# Serial_I2C_Bridge.net
KiCad netlist of a schematic drawn in EAGLE
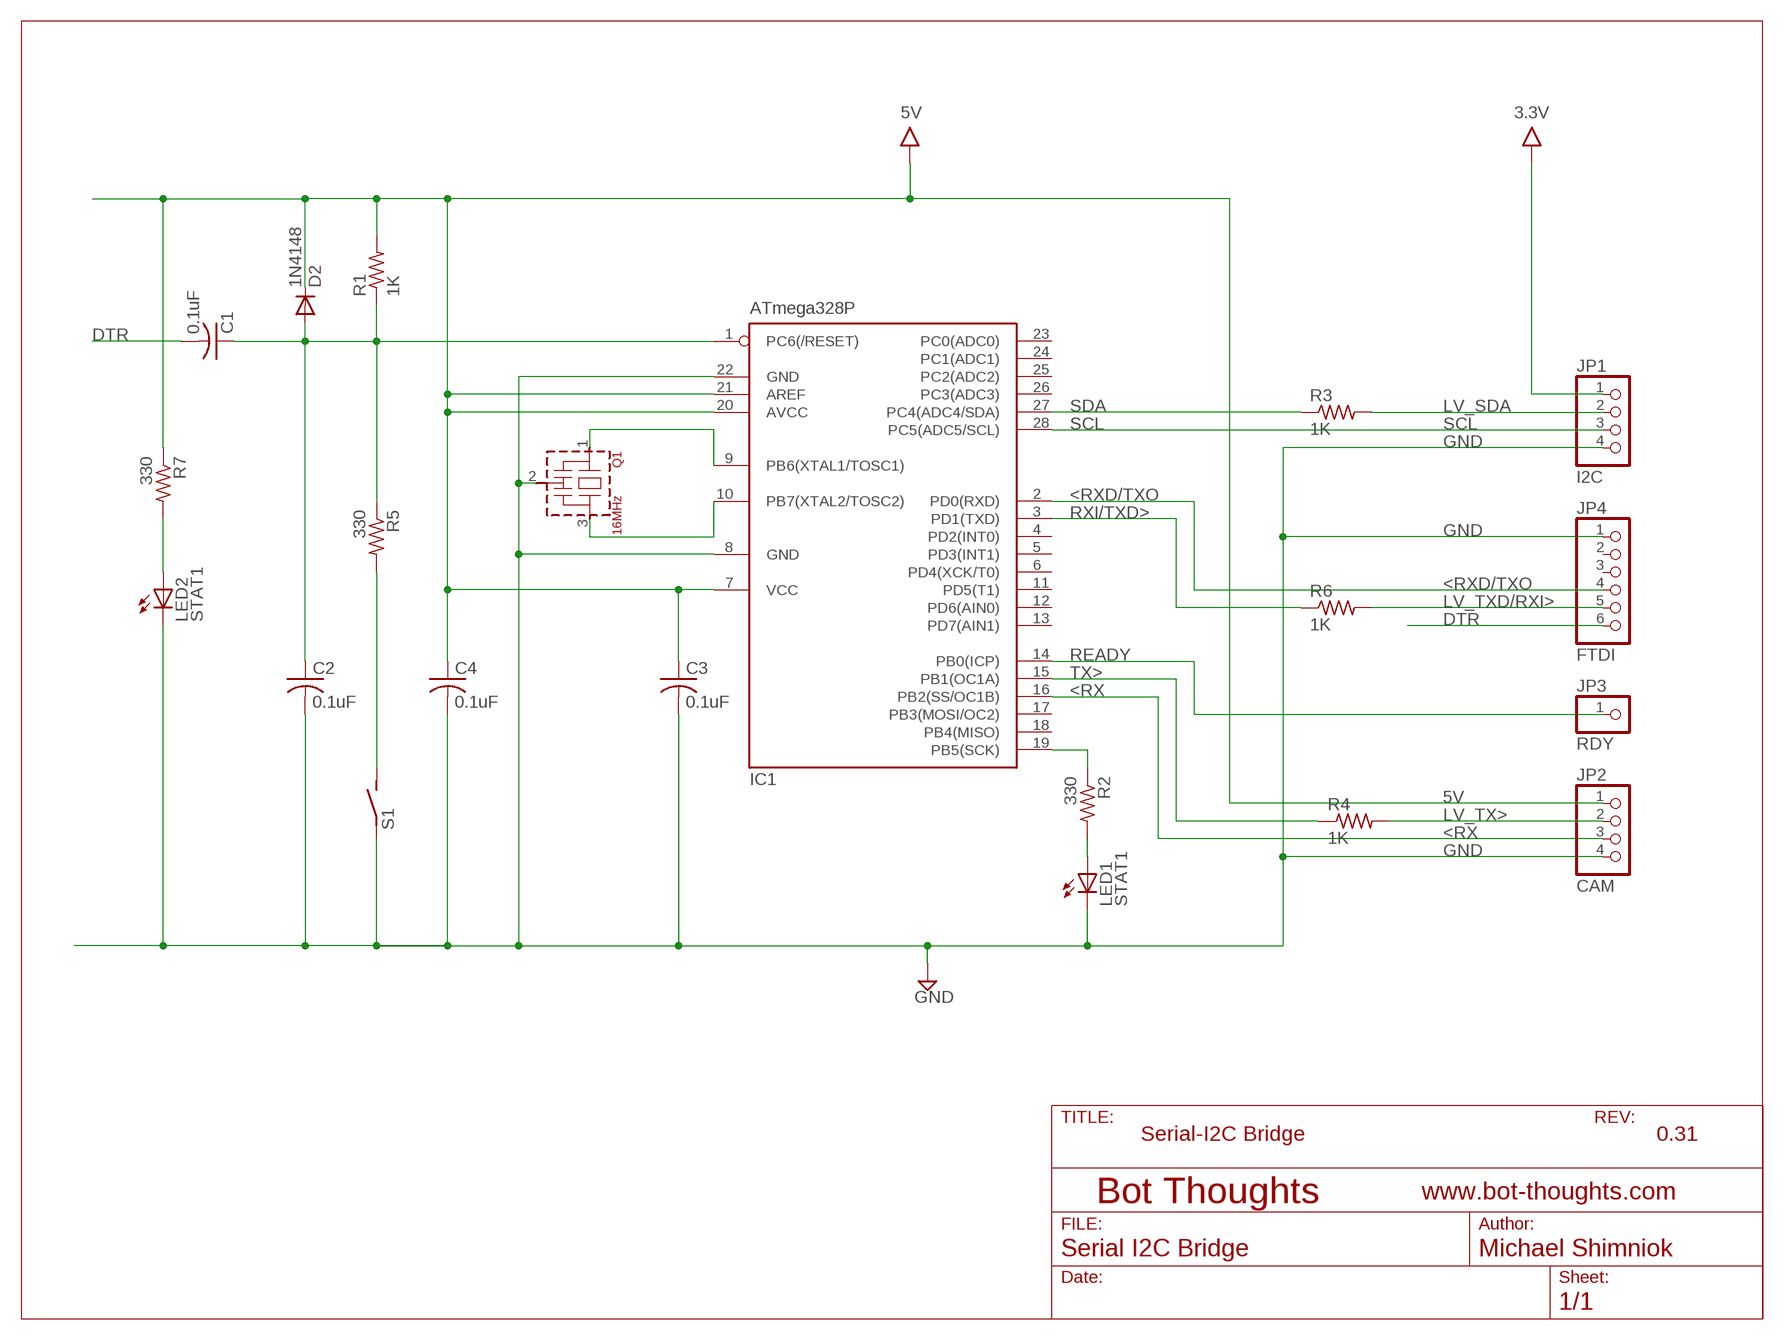
[diagram p0: schematic, sheet 1]

(export (version "E")
  (design (tool "Eeschema 10.0.6"))
  (components
    (comp (ref "C1")
      (value "0.1uF")
      (footprint "eagle-import:C0805")
      (fields (field (name "PARTNO") "CC0603ZRY5V7BB104"))
      (libsource (lib "eagle-import") (part "C-USC0805"))
    )
    (comp (ref "C2")
      (value "0.1uF")
      (footprint "eagle-import:C0805")
      (fields (field (name "PARTNO") "C1608X5R0J105K"))
      (libsource (lib "eagle-import") (part "C-USC0805"))
    )
    (comp (ref "C3")
      (value "0.1uF")
      (footprint "eagle-import:C0805")
      (fields (field (name "PARTNO") "C1608X5R0J105K"))
      (libsource (lib "eagle-import") (part "C-USC0805"))
    )
    (comp (ref "C4")
      (value "0.1uF")
      (footprint "eagle-import:C0805")
      (fields (field (name "PARTNO") "C1608X5R0J105K"))
      (libsource (lib "eagle-import") (part "C-USC0805"))
    )
    (comp (ref "D2")
      (value "1N4148")
      (footprint "eagle-import:DO35-7")
      (libsource (lib "eagle-import") (part "1N4148DO35-7"))
    )
    (comp (ref "IC1")
      (value "ATmega328P")
      (footprint "eagle-import:DIL28-3")
      (fields (field (name "PARTNO") "DEV-10524"))
      (libsource (lib "eagle-import") (part "MEGA8-P"))
    )
    (comp (ref "JP1")
      (value "I2C")
      (footprint "eagle-import:1X04-S")
      (fields (field (name "PARTNO") "2211S-04G"))
      (libsource (lib "eagle-import") (part "PINHD-1X04_2.54-S"))
    )
    (comp (ref "JP2")
      (value "CAM")
      (footprint "eagle-import:1X04-S")
      (fields (field (name "PARTNO") "2211S-04G"))
      (libsource (lib "eagle-import") (part "PINHD-1X04_2.54-S"))
    )
    (comp (ref "JP3")
      (value "RDY")
      (footprint "eagle-import:1X01-S")
      (libsource (lib "eagle-import") (part "PINHD-1X01_2.54-S"))
    )
    (comp (ref "JP4")
      (value "FTDI")
      (footprint "eagle-import:1X06-S")
      (fields (field (name "PARTNO") "2211S-06G"))
      (libsource (lib "eagle-import") (part "PINHD-1X06_2.54-S"))
    )
    (comp (ref "LED1")
      (value "STAT1")
      (footprint "eagle-import:LED3MM")
      (libsource (lib "eagle-import") (part "LED3MM"))
    )
    (comp (ref "LED2")
      (value "STAT1")
      (footprint "eagle-import:LED3MM")
      (libsource (lib "eagle-import") (part "LED3MM"))
    )
    (comp (ref "Q1")
      (value "16MHz")
      (footprint "eagle-import:CSTLS_G9")
      (fields (field (name "PARTNO") "AWCR-16.00MD"))
      (libsource (lib "eagle-import") (part "murata-resonators_CSTLS_G"))
    )
    (comp (ref "R1")
      (value "1K")
      (footprint "eagle-import:0204_5")
      (libsource (lib "eagle-import") (part "R-US_0204/5"))
    )
    (comp (ref "R2")
      (value "330")
      (footprint "eagle-import:0204_5")
      (fields (field (name "PARTNO") "CRCW0603330RJNEA"))
      (libsource (lib "eagle-import") (part "R-US_0204/5"))
    )
    (comp (ref "R3")
      (value "1K")
      (footprint "eagle-import:0204_5")
      (fields (field (name "PARTNO") "CRCW0603330RJNEA"))
      (libsource (lib "eagle-import") (part "R-US_0204/5"))
    )
    (comp (ref "R4")
      (value "1K")
      (footprint "eagle-import:0204_5")
      (fields (field (name "PARTNO") "CRCW0603330RJNEA"))
      (libsource (lib "eagle-import") (part "R-US_0204/5"))
    )
    (comp (ref "R5")
      (value "330")
      (footprint "eagle-import:0204_5")
      (fields (field (name "PARTNO") "CRCW0603330RJNEA"))
      (libsource (lib "eagle-import") (part "R-US_0204/5"))
    )
    (comp (ref "R6")
      (value "1K")
      (footprint "eagle-import:0204_5")
      (fields (field (name "PARTNO") "CRCW0603330RJNEA"))
      (libsource (lib "eagle-import") (part "R-US_0204/5"))
    )
    (comp (ref "R7")
      (value "330")
      (footprint "eagle-import:0204_5")
      (fields (field (name "PARTNO") "CRCW0603330RJNEA"))
      (libsource (lib "eagle-import") (part "R-US_0204/5"))
    )
    (comp (ref "S1")
      (value "RESET\\")
      (footprint "eagle-import:EVQ11X09")
      (fields (field (name "PARTNO") "SALVAGE"))
      (libsource (lib "eagle-import") (part "SPST2EVQ11X09"))
    )
  )
  (nets
    (net (code "1") (name "/<RX") (class "Default")
      (node (ref "IC1") (pin "16") (pinfunction "PB2(SS/OC1B)_16") (pintype "bidirectional"))
      (node (ref "JP2") (pin "3") (pinfunction "3_3") (pintype "passive"))
    )
    (net (code "2") (name "/<RXD{slash}TXO") (class "Default")
      (node (ref "IC1") (pin "2") (pinfunction "PD0(RXD)_2") (pintype "bidirectional"))
      (node (ref "JP4") (pin "4") (pinfunction "4_4") (pintype "passive"))
    )
    (net (code "3") (name "/DTR") (class "Default")
      (node (ref "C1") (pin "2") (pinfunction "2_2") (pintype "passive"))
      (node (ref "JP4") (pin "6") (pinfunction "6_6") (pintype "passive"))
    )
    (net (code "4") (name "/LV_SDA") (class "Default")
      (node (ref "JP1") (pin "2") (pinfunction "2_2") (pintype "passive"))
      (node (ref "R3") (pin "2") (pinfunction "2_2") (pintype "passive"))
    )
    (net (code "5") (name "/LV_TX>") (class "Default")
      (node (ref "JP2") (pin "2") (pinfunction "2_2") (pintype "passive"))
      (node (ref "R4") (pin "2") (pinfunction "2_2") (pintype "passive"))
    )
    (net (code "6") (name "/LV_TXD{slash}RXI>") (class "Default")
      (node (ref "JP4") (pin "5") (pinfunction "5_5") (pintype "passive"))
      (node (ref "R6") (pin "2") (pinfunction "2_2") (pintype "passive"))
    )
    (net (code "7") (name "/READY") (class "Default")
      (node (ref "IC1") (pin "14") (pinfunction "PB0(ICP)_14") (pintype "bidirectional"))
      (node (ref "JP3") (pin "1") (pinfunction "1_1") (pintype "passive"))
    )
    (net (code "8") (name "/RXI{slash}TXD>") (class "Default")
      (node (ref "IC1") (pin "3") (pinfunction "PD1(TXD)_3") (pintype "bidirectional"))
      (node (ref "R6") (pin "1") (pinfunction "1_1") (pintype "passive"))
    )
    (net (code "9") (name "/SCL") (class "Default")
      (node (ref "IC1") (pin "28") (pinfunction "PC5(ADC5/SCL)_28") (pintype "bidirectional"))
      (node (ref "JP1") (pin "3") (pinfunction "3_3") (pintype "passive"))
    )
    (net (code "10") (name "/SDA") (class "Default")
      (node (ref "IC1") (pin "27") (pinfunction "PC4(ADC4/SDA)_27") (pintype "bidirectional"))
      (node (ref "R3") (pin "1") (pinfunction "1_1") (pintype "passive"))
    )
    (net (code "11") (name "/TX>") (class "Default")
      (node (ref "IC1") (pin "15") (pinfunction "PB1(OC1A)_15") (pintype "bidirectional"))
      (node (ref "R4") (pin "1") (pinfunction "1_1") (pintype "passive"))
    )
    (net (code "12") (name "3.3V") (class "Default")
      (node (ref "JP1") (pin "1") (pinfunction "1_1") (pintype "passive"))
    )
    (net (code "13") (name "5V") (class "Default")
      (node (ref "C3") (pin "1") (pinfunction "1_1") (pintype "passive"))
      (node (ref "C4") (pin "1") (pinfunction "1_1") (pintype "passive"))
      (node (ref "D2") (pin "C") (pinfunction "C_C") (pintype "passive"))
      (node (ref "IC1") (pin "20") (pinfunction "AVCC_20") (pintype "power_in"))
      (node (ref "IC1") (pin "21") (pinfunction "AREF_21") (pintype "passive"))
      (node (ref "IC1") (pin "7") (pinfunction "VCC_7") (pintype "power_in"))
      (node (ref "JP2") (pin "1") (pinfunction "1_1") (pintype "passive"))
      (node (ref "R1") (pin "2") (pinfunction "2_2") (pintype "passive"))
      (node (ref "R7") (pin "1") (pinfunction "1_1") (pintype "passive"))
    )
    (net (code "14") (name "GND") (class "Default")
      (node (ref "C2") (pin "2") (pinfunction "2_2") (pintype "passive"))
      (node (ref "C3") (pin "2") (pinfunction "2_2") (pintype "passive"))
      (node (ref "C4") (pin "2") (pinfunction "2_2") (pintype "passive"))
      (node (ref "IC1") (pin "22") (pinfunction "GND_22") (pintype "power_in"))
      (node (ref "IC1") (pin "8") (pinfunction "GND_8") (pintype "power_in"))
      (node (ref "JP1") (pin "4") (pinfunction "4_4") (pintype "passive"))
      (node (ref "JP2") (pin "4") (pinfunction "4_4") (pintype "passive"))
      (node (ref "JP4") (pin "1") (pinfunction "1_1") (pintype "passive"))
      (node (ref "LED1") (pin "K") (pinfunction "C_K") (pintype "passive"))
      (node (ref "LED2") (pin "K") (pinfunction "C_K") (pintype "passive"))
      (node (ref "Q1") (pin "2") (pinfunction "VSS_2") (pintype "power_in"))
      (node (ref "S1") (pin "1") (pinfunction "1_1") (pintype "passive"))
    )
    (net (code "15") (name "Net-(IC1-PB5(SCK))") (class "Default")
      (node (ref "IC1") (pin "19") (pinfunction "PB5(SCK)_19") (pintype "bidirectional"))
      (node (ref "R2") (pin "1") (pinfunction "1_1") (pintype "passive"))
    )
    (net (code "16") (name "Net-(IC1-PB6(XTAL1{slash}TOSC1))") (class "Default")
      (node (ref "IC1") (pin "9") (pinfunction "PB6(XTAL1/TOSC1)_9") (pintype "bidirectional"))
      (node (ref "Q1") (pin "1") (pinfunction "1_1") (pintype "output"))
    )
    (net (code "17") (name "Net-(IC1-PB7(XTAL2{slash}TOSC2))") (class "Default")
      (node (ref "IC1") (pin "10") (pinfunction "PB7(XTAL2/TOSC2)_10") (pintype "bidirectional"))
      (node (ref "Q1") (pin "3") (pinfunction "3_3") (pintype "input"))
    )
    (net (code "18") (name "Net-(IC1-PC6({slash}RESET))") (class "Default")
      (node (ref "C1") (pin "1") (pinfunction "1_1") (pintype "passive"))
      (node (ref "C2") (pin "1") (pinfunction "1_1") (pintype "passive"))
      (node (ref "D2") (pin "A") (pinfunction "A_A") (pintype "passive"))
      (node (ref "IC1") (pin "1") (pinfunction "PC6(/RESET)_1") (pintype "bidirectional"))
      (node (ref "R1") (pin "1") (pinfunction "1_1") (pintype "passive"))
      (node (ref "R5") (pin "1") (pinfunction "1_1") (pintype "passive"))
    )
    (net (code "19") (name "Net-(LED1-PadA)") (class "Default")
      (node (ref "LED1") (pin "A") (pinfunction "A_A") (pintype "passive"))
      (node (ref "R2") (pin "2") (pinfunction "2_2") (pintype "passive"))
    )
    (net (code "20") (name "Net-(LED2-PadA)") (class "Default")
      (node (ref "LED2") (pin "A") (pinfunction "A_A") (pintype "passive"))
      (node (ref "R7") (pin "2") (pinfunction "2_2") (pintype "passive"))
    )
    (net (code "21") (name "Net-(R5-Pad2)") (class "Default")
      (node (ref "R5") (pin "2") (pinfunction "2_2") (pintype "passive"))
      (node (ref "S1") (pin "2") (pinfunction "2_2") (pintype "passive"))
    )
    (net (code "22") (name "unconnected-(IC1-PB3(MOSI{slash}OC2)-Pad17)") (class "Default")
      (node (ref "IC1") (pin "17") (pinfunction "PB3(MOSI/OC2)_17") (pintype "bidirectional"))
    )
    (net (code "23") (name "unconnected-(IC1-PB4(MISO)-Pad18)") (class "Default")
      (node (ref "IC1") (pin "18") (pinfunction "PB4(MISO)_18") (pintype "bidirectional"))
    )
    (net (code "24") (name "unconnected-(IC1-PC0(ADC0)-Pad23)") (class "Default")
      (node (ref "IC1") (pin "23") (pinfunction "PC0(ADC0)_23") (pintype "bidirectional"))
    )
    (net (code "25") (name "unconnected-(IC1-PC1(ADC1)-Pad24)") (class "Default")
      (node (ref "IC1") (pin "24") (pinfunction "PC1(ADC1)_24") (pintype "bidirectional"))
    )
    (net (code "26") (name "unconnected-(IC1-PC2(ADC2)-Pad25)") (class "Default")
      (node (ref "IC1") (pin "25") (pinfunction "PC2(ADC2)_25") (pintype "bidirectional"))
    )
    (net (code "27") (name "unconnected-(IC1-PC3(ADC3)-Pad26)") (class "Default")
      (node (ref "IC1") (pin "26") (pinfunction "PC3(ADC3)_26") (pintype "bidirectional"))
    )
    (net (code "28") (name "unconnected-(IC1-PD2(INT0)-Pad4)") (class "Default")
      (node (ref "IC1") (pin "4") (pinfunction "PD2(INT0)_4") (pintype "bidirectional"))
    )
    (net (code "29") (name "unconnected-(IC1-PD3(INT1)-Pad5)") (class "Default")
      (node (ref "IC1") (pin "5") (pinfunction "PD3(INT1)_5") (pintype "bidirectional"))
    )
    (net (code "30") (name "unconnected-(IC1-PD4(XCK{slash}T0)-Pad6)") (class "Default")
      (node (ref "IC1") (pin "6") (pinfunction "PD4(XCK/T0)_6") (pintype "bidirectional"))
    )
    (net (code "31") (name "unconnected-(IC1-PD5(T1)-Pad11)") (class "Default")
      (node (ref "IC1") (pin "11") (pinfunction "PD5(T1)_11") (pintype "bidirectional"))
    )
    (net (code "32") (name "unconnected-(IC1-PD6(AIN0)-Pad12)") (class "Default")
      (node (ref "IC1") (pin "12") (pinfunction "PD6(AIN0)_12") (pintype "bidirectional"))
    )
    (net (code "33") (name "unconnected-(IC1-PD7(AIN1)-Pad13)") (class "Default")
      (node (ref "IC1") (pin "13") (pinfunction "PD7(AIN1)_13") (pintype "bidirectional"))
    )
    (net (code "34") (name "unconnected-(JP4-Pad2)") (class "Default")
      (node (ref "JP4") (pin "2") (pinfunction "2_2") (pintype "passive"))
    )
    (net (code "35") (name "unconnected-(JP4-Pad3)") (class "Default")
      (node (ref "JP4") (pin "3") (pinfunction "3_3") (pintype "passive"))
    )
  )
)
